# SCH_HackerCard_2024-08-18.net
KiCad netlist of a schematic drawn in EasyEDA
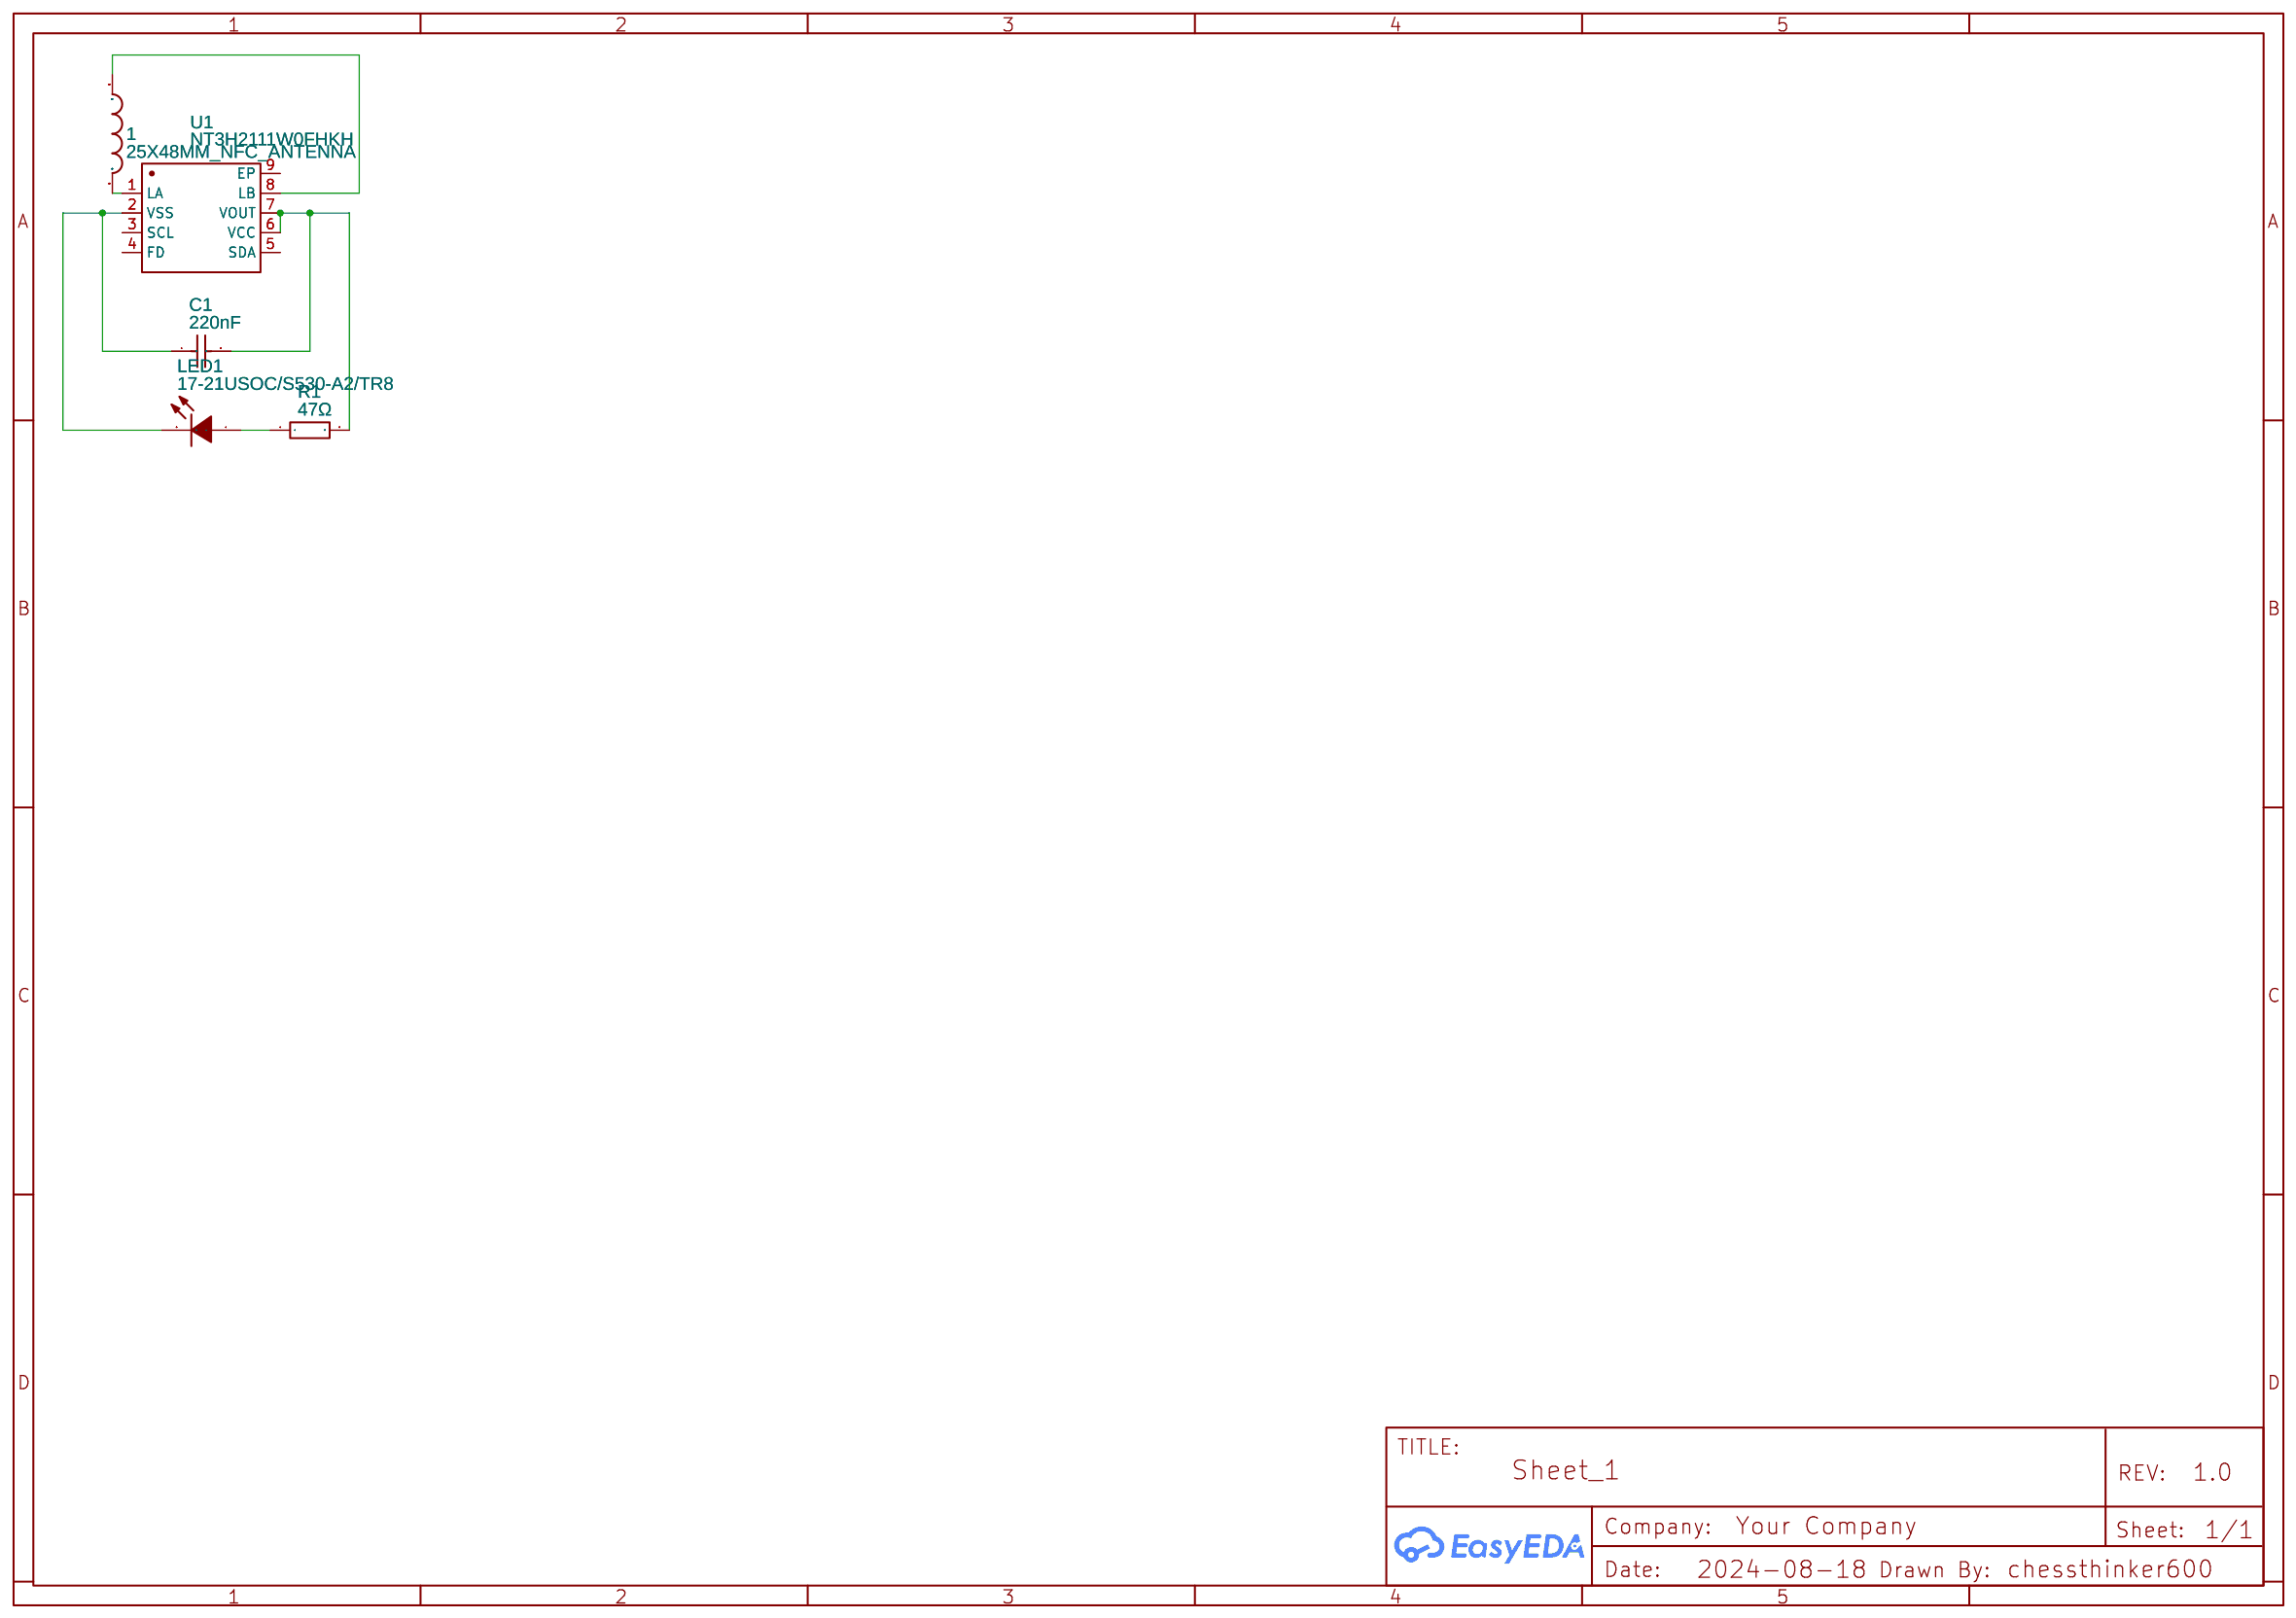
[diagram p0: schematic sheet]

(export (version "E")
  (design (tool "Eeschema 10.0.6"))
  (components
    (comp (ref "1") (value "25X48MM_NFC_ANTENNA") (libsource (lib "") (part "25X48MM_NFC_ANTENNA")))
    (comp (ref "C1")
      (value "220nF")
      (fields
        (field (name "Manufacturer Part") "CL10B224KA8NNNC")
        (field (name "Manufacturer") "SAMSUNG(三星)")
      )
      (libsource (lib "") (part "CL10B224KA8NNNC"))
    )
    (comp (ref "LED1")
      (value "17-21USOC/S530-A2/TR8")
      (fields (field (name "Manufacturer") "EVERLIGHT(亿光)"))
      (libsource (lib "") (part "17-21USOC/S530-A2/TR8"))
    )
    (comp (ref "R1")
      (value "47Ω")
      (fields
        (field (name "Manufacturer Part") "0603WAF470JT5E")
        (field (name "Manufacturer") "UNI-ROYAL(厚声)")
      )
      (libsource (lib "") (part "0603WAF470JT5E"))
    )
    (comp (ref "U1")
      (value "NT3H2111W0FHKH")
      (fields (field (name "Manufacturer") "NXP(恩智浦)"))
      (libsource (lib "") (part "NT3H2111W0FHKH"))
    )
  )
  (nets
    (net (code "1") (name "Net-(LED1-A)") (class "Default")
      (node (ref "LED1") (pin "1") (pinfunction "A_1") (pintype "unspecified"))
      (node (ref "R1") (pin "1") (pinfunction "1_1") (pintype "input"))
    )
    (net (code "2") (name "Net-(LED1-K)") (class "Default")
      (node (ref "C1") (pin "1") (pinfunction "1_1") (pintype "input"))
      (node (ref "LED1") (pin "2") (pinfunction "K_2") (pintype "unspecified"))
      (node (ref "U1") (pin "2") (pinfunction "VSS_2") (pintype "unspecified"))
    )
    (net (code "3") (name "Net-(U1-LA)") (class "Default")
      (node (ref "1") (pin "P$2") (pinfunction "P$2_P$2") (pintype "bidirectional"))
      (node (ref "U1") (pin "1") (pinfunction "LA_1") (pintype "unspecified"))
    )
    (net (code "4") (name "Net-(U1-LB)") (class "Default")
      (node (ref "1") (pin "P$1") (pinfunction "P$1_P$1") (pintype "bidirectional"))
      (node (ref "U1") (pin "8") (pinfunction "LB_8") (pintype "unspecified"))
    )
    (net (code "5") (name "Net-(U1-VCC)") (class "Default")
      (node (ref "C1") (pin "2") (pinfunction "2_2") (pintype "input"))
      (node (ref "R1") (pin "2") (pinfunction "2_2") (pintype "input"))
      (node (ref "U1") (pin "6") (pinfunction "VCC_6") (pintype "unspecified"))
      (node (ref "U1") (pin "7") (pinfunction "VOUT_7") (pintype "unspecified"))
    )
    (net (code "6") (name "unconnected-(U1-EP-Pad9)") (class "Default")
      (node (ref "U1") (pin "9") (pinfunction "EP_9") (pintype "unspecified"))
    )
    (net (code "7") (name "unconnected-(U1-FD-Pad4)") (class "Default")
      (node (ref "U1") (pin "4") (pinfunction "FD_4") (pintype "unspecified"))
    )
    (net (code "8") (name "unconnected-(U1-SCL-Pad3)") (class "Default")
      (node (ref "U1") (pin "3") (pinfunction "SCL_3") (pintype "unspecified"))
    )
    (net (code "9") (name "unconnected-(U1-SDA-Pad5)") (class "Default")
      (node (ref "U1") (pin "5") (pinfunction "SDA_5") (pintype "unspecified"))
    )
  )
)
